# CODEC.net
KiCad netlist of a schematic drawn in Altium Designer
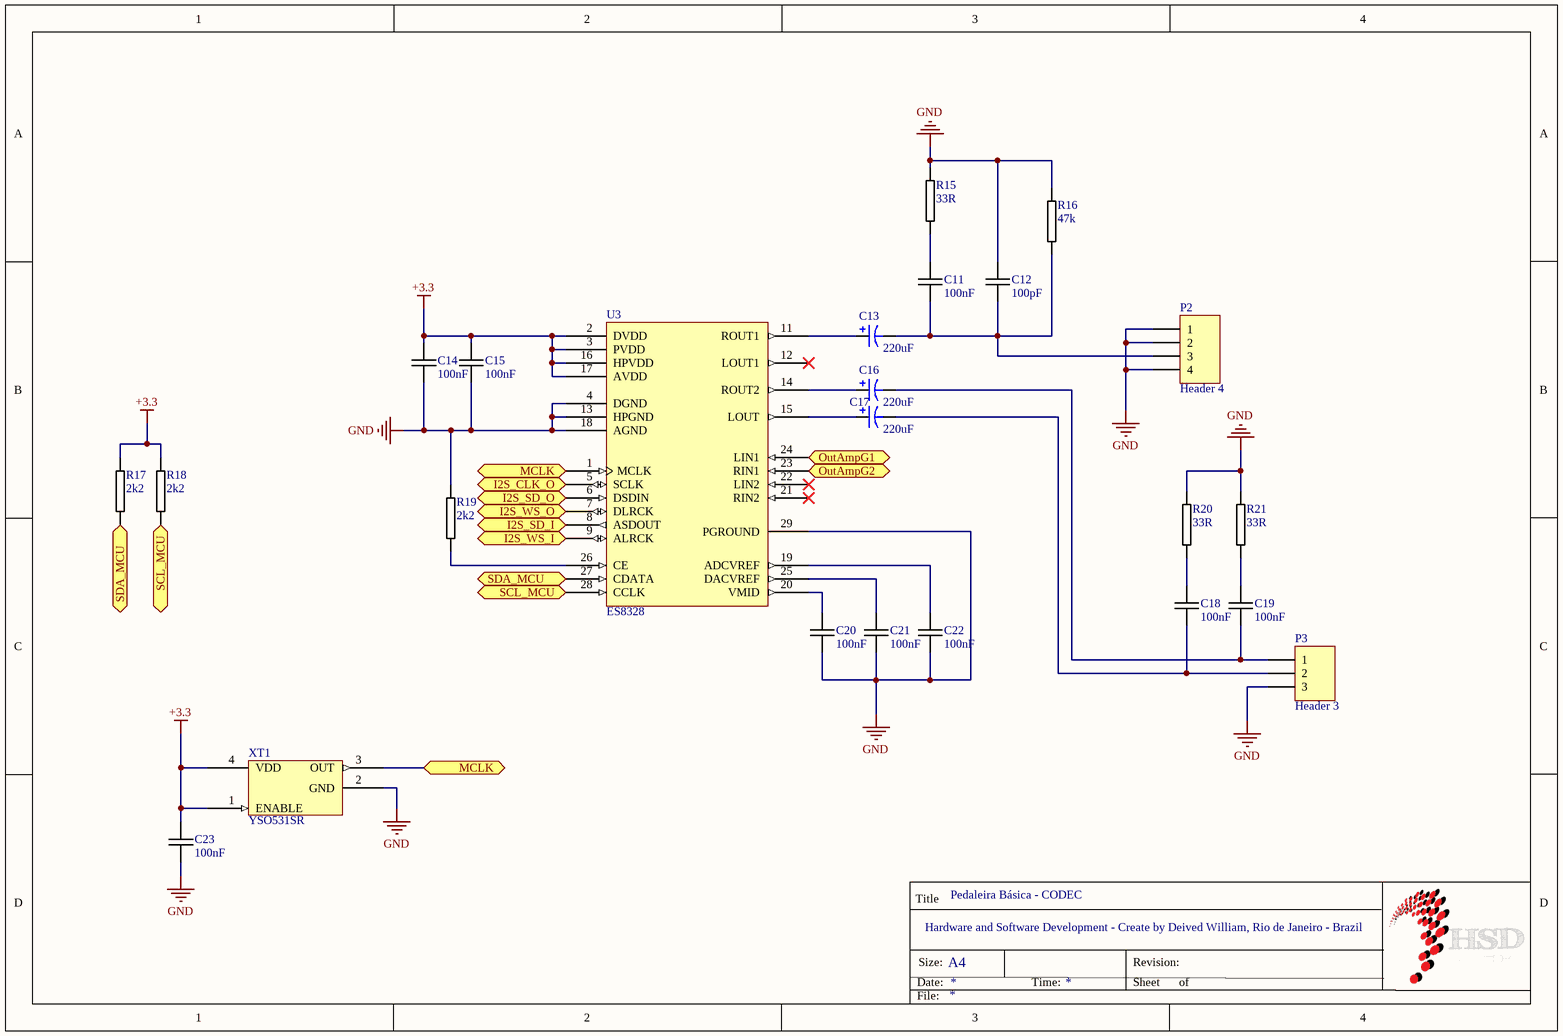
[diagram p0: CODEC.SchDoc]

(export (version "E")
  (design (tool "Eeschema 10.0.6"))
  (components
    (comp (ref "C11")
      (value "100nF")
      (footprint "0603C-GENERIC")
      (description "CAPACITOR 0603 CERAMIC")
      (fields
        (field (name "MANUFACTURER PART NUMBER") "C1608X7R1E104K")
        (field (name "MANUFACTURER") "TDK Corporation")
      )
      (libsource (lib "vh_altium_library") (part "0603C-100NF-25V-X7R-TDK"))
    )
    (comp (ref "C12")
      (value "100pF")
      (footprint "0603C-GENERIC")
      (description "CAPACITOR 0603 CERAMIC")
      (fields
        (field (name "MANUFACTURER PART NUMBER") "C1608X7R1E104K")
        (field (name "MANUFACTURER") "TDK Corporation")
      )
      (libsource (lib "vh_altium_library") (part "0603C-100NF-25V-X7R-TDK"))
    )
    (comp (ref "C13")
      (value "220uF")
      (footprint "D")
      (fields (field (name "PUBLISHER") "Altium Limited"))
      (libsource (lib "Vishay Sprague Tantalum Chip Capacitor") (part "CC106D004M"))
    )
    (comp (ref "C14")
      (value "100nF")
      (footprint "0603C-GENERIC")
      (description "CAPACITOR 0603 CERAMIC")
      (fields
        (field (name "MANUFACTURER PART NUMBER") "C1608X7R1E104K")
        (field (name "MANUFACTURER") "TDK Corporation")
      )
      (libsource (lib "vh_altium_library") (part "0603C-100NF-25V-X7R-TDK"))
    )
    (comp (ref "C15")
      (value "100nF")
      (footprint "0603C-GENERIC")
      (description "CAPACITOR 0603 CERAMIC")
      (fields
        (field (name "MANUFACTURER PART NUMBER") "C1608X7R1E104K")
        (field (name "MANUFACTURER") "TDK Corporation")
      )
      (libsource (lib "vh_altium_library") (part "0603C-100NF-25V-X7R-TDK"))
    )
    (comp (ref "C16")
      (value "220uF")
      (footprint "D")
      (fields (field (name "PUBLISHER") "Altium Limited"))
      (libsource (lib "Vishay Sprague Tantalum Chip Capacitor") (part "CC106D004M"))
    )
    (comp (ref "C17")
      (value "220uF")
      (footprint "D")
      (fields (field (name "PUBLISHER") "Altium Limited"))
      (libsource (lib "Vishay Sprague Tantalum Chip Capacitor") (part "CC106D004M"))
    )
    (comp (ref "C18")
      (value "100nF")
      (footprint "0603C-GENERIC")
      (description "CAPACITOR 0603 CERAMIC")
      (fields
        (field (name "MANUFACTURER PART NUMBER") "C1608X7R1E104K")
        (field (name "MANUFACTURER") "TDK Corporation")
      )
      (libsource (lib "vh_altium_library") (part "0603C-100NF-25V-X7R-TDK"))
    )
    (comp (ref "C19")
      (value "100nF")
      (footprint "0603C-GENERIC")
      (description "CAPACITOR 0603 CERAMIC")
      (fields
        (field (name "MANUFACTURER PART NUMBER") "C1608X7R1E104K")
        (field (name "MANUFACTURER") "TDK Corporation")
      )
      (libsource (lib "vh_altium_library") (part "0603C-100NF-25V-X7R-TDK"))
    )
    (comp (ref "C20")
      (value "100nF")
      (footprint "0603C-GENERIC")
      (description "CAPACITOR 0603 CERAMIC")
      (fields
        (field (name "MANUFACTURER PART NUMBER") "C1608X7R1E104K")
        (field (name "MANUFACTURER") "TDK Corporation")
      )
      (libsource (lib "vh_altium_library") (part "0603C-100NF-25V-X7R-TDK"))
    )
    (comp (ref "C21")
      (value "100nF")
      (footprint "0603C-GENERIC")
      (description "CAPACITOR 0603 CERAMIC")
      (fields
        (field (name "MANUFACTURER PART NUMBER") "C1608X7R1E104K")
        (field (name "MANUFACTURER") "TDK Corporation")
      )
      (libsource (lib "vh_altium_library") (part "0603C-100NF-25V-X7R-TDK"))
    )
    (comp (ref "C22")
      (value "100nF")
      (footprint "0603C-GENERIC")
      (description "CAPACITOR 0603 CERAMIC")
      (fields
        (field (name "MANUFACTURER PART NUMBER") "C1608X7R1E104K")
        (field (name "MANUFACTURER") "TDK Corporation")
      )
      (libsource (lib "vh_altium_library") (part "0603C-100NF-25V-X7R-TDK"))
    )
    (comp (ref "C23")
      (value "100nF")
      (footprint "0603C-GENERIC")
      (description "CAPACITOR 0603 CERAMIC")
      (fields
        (field (name "MANUFACTURER PART NUMBER") "C1608X7R1E104K")
        (field (name "MANUFACTURER") "TDK Corporation")
      )
      (libsource (lib "vh_altium_library") (part "0603C-100NF-25V-X7R-TDK"))
    )
    (comp (ref "P2")
      (value "Header 4")
      (footprint "JACK P10 PLUG")
      (description "Header, 4-Pin")
      (fields (field (name "PUBLISHER") "Altium Limited"))
      (libsource (lib "Miscellaneous Connectors") (part "Header 4"))
    )
    (comp (ref "P3")
      (value "Header 3")
      (footprint "HDR1X3")
      (description "Header, 3-Pin")
      (fields (field (name "PUBLISHER") "Altium Limited"))
      (libsource (lib "Miscellaneous Connectors") (part "Header 3"))
    )
    (comp (ref "R15")
      (value "33R")
      (footprint "0603R-100")
      (description "GENERIC RESISTOR 0603")
      (fields
        (field (name "MANUFACTURER PART NUMBER") "RMCF 1/16 100 1% R")
        (field (name "MANUFACTURER") "Stackpole Electronics Inc")
      )
      (libsource (lib "vh_altium_library") (part "0603R-100"))
    )
    (comp (ref "R16")
      (value "47k")
      (footprint "0603R-100")
      (description "GENERIC RESISTOR 0603")
      (fields
        (field (name "MANUFACTURER PART NUMBER") "RMCF 1/16 100 1% R")
        (field (name "MANUFACTURER") "Stackpole Electronics Inc")
      )
      (libsource (lib "vh_altium_library") (part "0603R-100"))
    )
    (comp (ref "R17")
      (value "2k2")
      (footprint "0603R-100")
      (description "GENERIC RESISTOR 0603")
      (fields
        (field (name "MANUFACTURER PART NUMBER") "RMCF 1/16 100 1% R")
        (field (name "MANUFACTURER") "Stackpole Electronics Inc")
      )
      (libsource (lib "vh_altium_library") (part "0603R-100"))
    )
    (comp (ref "R18")
      (value "2k2")
      (footprint "0603R-100")
      (description "GENERIC RESISTOR 0603")
      (fields
        (field (name "MANUFACTURER PART NUMBER") "RMCF 1/16 100 1% R")
        (field (name "MANUFACTURER") "Stackpole Electronics Inc")
      )
      (libsource (lib "vh_altium_library") (part "0603R-100"))
    )
    (comp (ref "R19")
      (value "2k2")
      (footprint "0603R-100")
      (description "GENERIC RESISTOR 0603")
      (fields
        (field (name "MANUFACTURER PART NUMBER") "RMCF 1/16 100 1% R")
        (field (name "MANUFACTURER") "Stackpole Electronics Inc")
      )
      (libsource (lib "vh_altium_library") (part "0603R-100"))
    )
    (comp (ref "R20")
      (value "33R")
      (footprint "0603R-100")
      (description "GENERIC RESISTOR 0603")
      (fields
        (field (name "MANUFACTURER PART NUMBER") "RMCF 1/16 100 1% R")
        (field (name "MANUFACTURER") "Stackpole Electronics Inc")
      )
      (libsource (lib "vh_altium_library") (part "0603R-100"))
    )
    (comp (ref "R21")
      (value "33R")
      (footprint "0603R-100")
      (description "GENERIC RESISTOR 0603")
      (fields
        (field (name "MANUFACTURER PART NUMBER") "RMCF 1/16 100 1% R")
        (field (name "MANUFACTURER") "Stackpole Electronics Inc")
      )
      (libsource (lib "vh_altium_library") (part "0603R-100"))
    )
    (comp (ref "U3")
      (value "ES8328")
      (footprint "QFN-28L")
      (description "Low Power Estereo Audio Codec With HeadPhone Amplifier")
      (libsource (lib "Componentes Deived Projetos") (part "ES8328"))
    )
    (comp (ref "XT1")
      (value "YSO531SR")
      (footprint "CRISTAL")
      (description "Cristal Oscilator Active 1.8v - 3.3v")
      (libsource (lib "Componentes Deived Projetos") (part "YSO531SR"))
    )
  )
  (nets
    (net (code "1") (name "+3.3") (class "Default")
      (node (ref "C14") (pin "1") (pintype "passive"))
      (node (ref "C15") (pin "1") (pintype "passive"))
      (node (ref "C23") (pin "1") (pintype "passive"))
      (node (ref "R17") (pin "1") (pintype "passive"))
      (node (ref "R18") (pin "1") (pintype "passive"))
      (node (ref "U3") (pin "16") (pinfunction "HPVDD_16") (pintype "power_in"))
      (node (ref "U3") (pin "17") (pinfunction "AVDD_17") (pintype "passive"))
      (node (ref "U3") (pin "2") (pinfunction "DVDD_2") (pintype "power_in"))
      (node (ref "U3") (pin "3") (pinfunction "PVDD_3") (pintype "power_in"))
      (node (ref "XT1") (pin "1") (pinfunction "ENABLE_1") (pintype "input"))
      (node (ref "XT1") (pin "4") (pinfunction "VDD_4") (pintype "passive"))
    )
    (net (code "2") (name "/I2S_CLK_O") (class "Default")
      (node (ref "U3") (pin "5") (pinfunction "SCLK_5") (pintype "bidirectional"))
    )
    (net (code "3") (name "/I2S_SD_I") (class "Default")
      (node (ref "U3") (pin "8") (pinfunction "ASDOUT_8") (pintype "output"))
    )
    (net (code "4") (name "/I2S_SD_O") (class "Default")
      (node (ref "U3") (pin "6") (pinfunction "DSDIN_6") (pintype "input"))
    )
    (net (code "5") (name "/I2S_WS_I") (class "Default")
      (node (ref "U3") (pin "9") (pinfunction "ALRCK_9") (pintype "bidirectional"))
    )
    (net (code "6") (name "/I2S_WS_O") (class "Default")
      (node (ref "U3") (pin "7") (pinfunction "DLRCK_7") (pintype "bidirectional"))
    )
    (net (code "7") (name "/MCLK") (class "Default")
      (node (ref "U3") (pin "1") (pinfunction "MCLK_1") (pintype "input"))
      (node (ref "XT1") (pin "3") (pinfunction "OUT_3") (pintype "output"))
    )
    (net (code "8") (name "/OutAmpG1") (class "Default")
      (node (ref "U3") (pin "24") (pinfunction "LIN1_24") (pintype "input"))
    )
    (net (code "9") (name "/OutAmpG2") (class "Default")
      (node (ref "U3") (pin "23") (pinfunction "RIN1_23") (pintype "input"))
    )
    (net (code "10") (name "/SCL_MCU") (class "Default")
      (node (ref "R18") (pin "2") (pintype "passive"))
      (node (ref "U3") (pin "28") (pinfunction "CCLK_28") (pintype "input"))
    )
    (net (code "11") (name "/SDA_MCU") (class "Default")
      (node (ref "R17") (pin "2") (pintype "passive"))
      (node (ref "U3") (pin "27") (pinfunction "CDATA_27") (pintype "input"))
    )
    (net (code "12") (name "GND") (class "Default")
      (node (ref "C12") (pin "1") (pintype "passive"))
      (node (ref "C14") (pin "2") (pintype "passive"))
      (node (ref "C15") (pin "2") (pintype "passive"))
      (node (ref "C20") (pin "2") (pintype "passive"))
      (node (ref "C21") (pin "2") (pintype "passive"))
      (node (ref "C22") (pin "2") (pintype "passive"))
      (node (ref "C23") (pin "2") (pintype "passive"))
      (node (ref "P2") (pin "1") (pinfunction "1_1") (pintype "passive"))
      (node (ref "P2") (pin "2") (pinfunction "2_2") (pintype "passive"))
      (node (ref "P2") (pin "4") (pinfunction "4_4") (pintype "passive"))
      (node (ref "P3") (pin "3") (pinfunction "3_3") (pintype "passive"))
      (node (ref "R15") (pin "1") (pintype "passive"))
      (node (ref "R16") (pin "1") (pintype "passive"))
      (node (ref "R19") (pin "2") (pintype "passive"))
      (node (ref "R20") (pin "1") (pintype "passive"))
      (node (ref "R21") (pin "1") (pintype "passive"))
      (node (ref "U3") (pin "13") (pinfunction "HPGND_13") (pintype "passive"))
      (node (ref "U3") (pin "18") (pinfunction "AGND_18") (pintype "passive"))
      (node (ref "U3") (pin "29") (pinfunction "PGROUND_29") (pintype "passive"))
      (node (ref "U3") (pin "4") (pinfunction "DGND_4") (pintype "passive"))
      (node (ref "XT1") (pin "2") (pinfunction "GND_2") (pintype "passive"))
    )
    (net (code "13") (name "Net-(C11-Pad1)") (class "Default")
      (node (ref "C11") (pin "1") (pintype "passive"))
      (node (ref "R15") (pin "2") (pintype "passive"))
    )
    (net (code "14") (name "Net-(C11-Pad2)") (class "Default")
      (node (ref "C11") (pin "2") (pintype "passive"))
      (node (ref "C12") (pin "2") (pintype "passive"))
      (node (ref "C13") (pin "2") (pinfunction "2_2") (pintype "passive"))
      (node (ref "P2") (pin "3") (pinfunction "3_3") (pintype "passive"))
      (node (ref "R16") (pin "2") (pintype "passive"))
    )
    (net (code "15") (name "Net-(C16-Pad2)") (class "Default")
      (node (ref "C16") (pin "2") (pinfunction "2_2") (pintype "passive"))
      (node (ref "C19") (pin "2") (pintype "passive"))
      (node (ref "P3") (pin "1") (pinfunction "1_1") (pintype "passive"))
    )
    (net (code "16") (name "Net-(C17-Pad2)") (class "Default")
      (node (ref "C17") (pin "2") (pinfunction "2_2") (pintype "passive"))
      (node (ref "C18") (pin "2") (pintype "passive"))
      (node (ref "P3") (pin "2") (pinfunction "2_2") (pintype "passive"))
    )
    (net (code "17") (name "Net-(C18-Pad1)") (class "Default")
      (node (ref "C18") (pin "1") (pintype "passive"))
      (node (ref "R20") (pin "2") (pintype "passive"))
    )
    (net (code "18") (name "Net-(C19-Pad1)") (class "Default")
      (node (ref "C19") (pin "1") (pintype "passive"))
      (node (ref "R21") (pin "2") (pintype "passive"))
    )
    (net (code "19") (name "Net-(U3-ADCVREF)") (class "Default")
      (node (ref "C22") (pin "1") (pintype "passive"))
      (node (ref "U3") (pin "19") (pinfunction "ADCVREF_19") (pintype "output"))
    )
    (net (code "20") (name "Net-(U3-CE)") (class "Default")
      (node (ref "R19") (pin "1") (pintype "passive"))
      (node (ref "U3") (pin "26") (pinfunction "CE_26") (pintype "input"))
    )
    (net (code "21") (name "Net-(U3-DACVREF)") (class "Default")
      (node (ref "C21") (pin "1") (pintype "passive"))
      (node (ref "U3") (pin "25") (pinfunction "DACVREF_25") (pintype "output"))
    )
    (net (code "22") (name "Net-(U3-LOUT)") (class "Default")
      (node (ref "C17") (pin "1") (pinfunction "1_1") (pintype "passive"))
      (node (ref "U3") (pin "15") (pinfunction "LOUT_15") (pintype "output"))
    )
    (net (code "23") (name "Net-(U3-ROUT1)") (class "Default")
      (node (ref "C13") (pin "1") (pinfunction "1_1") (pintype "passive"))
      (node (ref "U3") (pin "11") (pinfunction "ROUT1_11") (pintype "output"))
    )
    (net (code "24") (name "Net-(U3-ROUT2)") (class "Default")
      (node (ref "C16") (pin "1") (pinfunction "1_1") (pintype "passive"))
      (node (ref "U3") (pin "14") (pinfunction "ROUT2_14") (pintype "output"))
    )
    (net (code "25") (name "Net-(U3-VMID)") (class "Default")
      (node (ref "C20") (pin "1") (pintype "passive"))
      (node (ref "U3") (pin "20") (pinfunction "VMID_20") (pintype "output"))
    )
    (net (code "26") (name "unconnected-(U3-LIN2-Pad22)") (class "Default")
      (node (ref "U3") (pin "22") (pinfunction "LIN2_22") (pintype "input+no_connect"))
    )
    (net (code "27") (name "unconnected-(U3-LOUT1-Pad12)") (class "Default")
      (node (ref "U3") (pin "12") (pinfunction "LOUT1_12") (pintype "output+no_connect"))
    )
    (net (code "28") (name "unconnected-(U3-RIN2-Pad21)") (class "Default")
      (node (ref "U3") (pin "21") (pinfunction "RIN2_21") (pintype "input+no_connect"))
    )
  )
)
